# Sheet3_MCU.net
KiCad netlist of a schematic drawn in Altium Designer
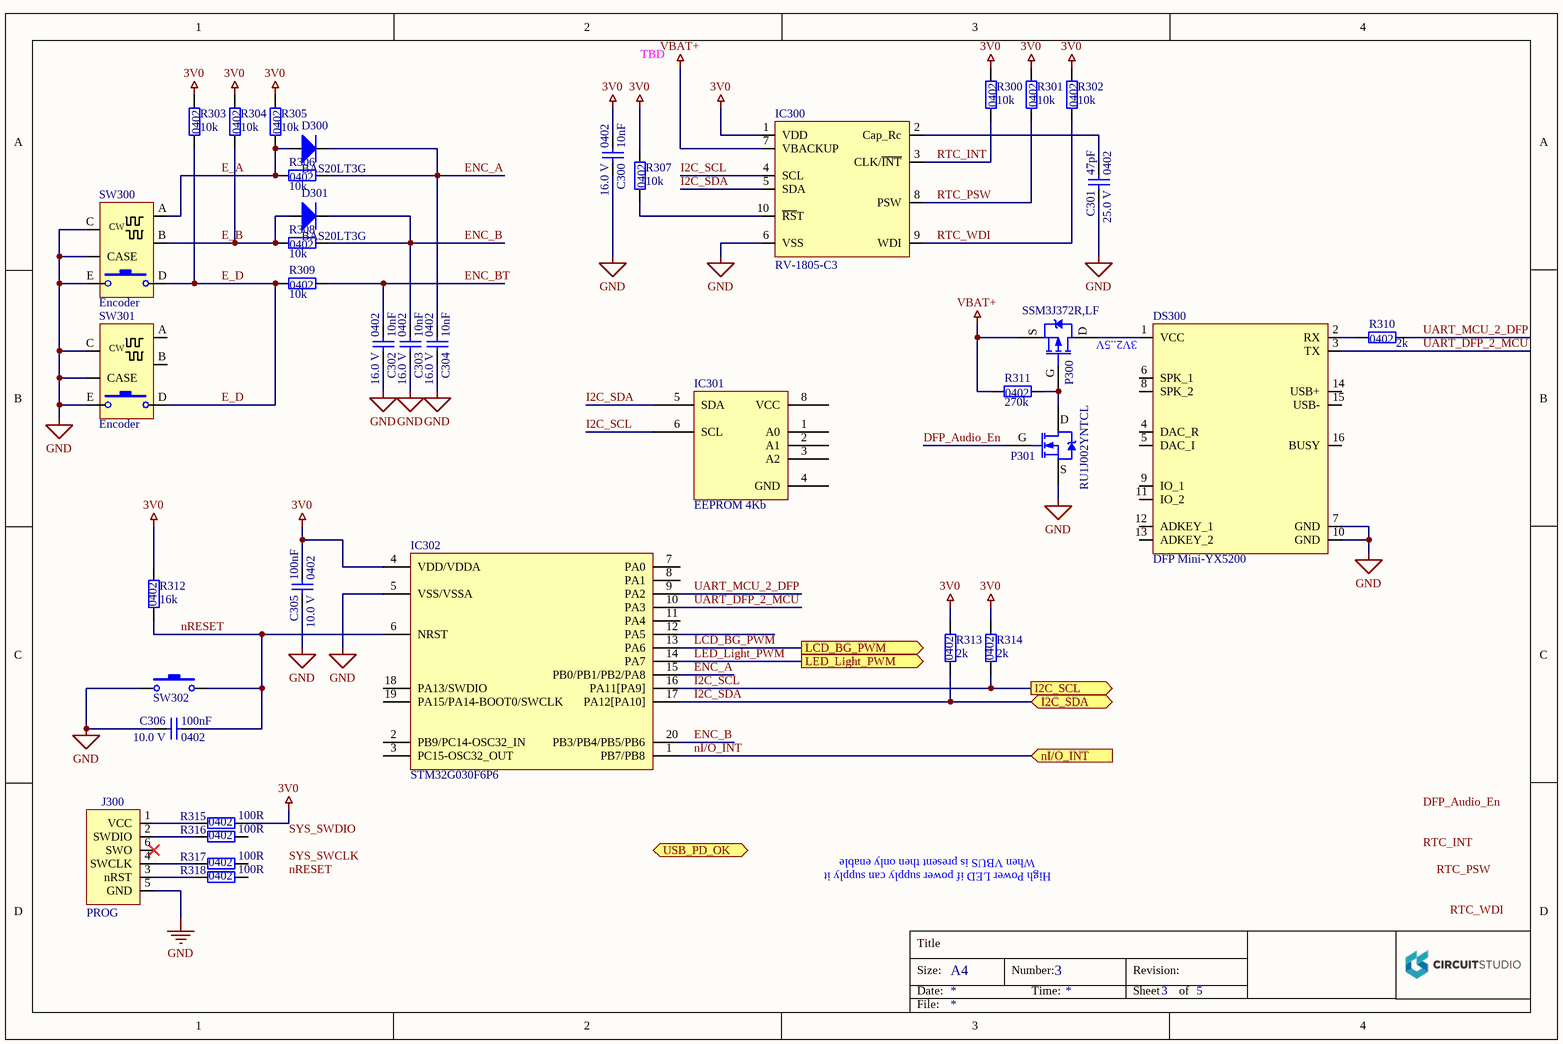
[diagram p0: Sheet3_MCU.SchDoc]

(export (version "E")
  (design (tool "Eeschema 10.0.6"))
  (components
    (comp (ref "C300")
      (value "C 10nF 0402 16V")
      (footprint "0402")
      (description "CAP CER 10000PF 16V Y5V 0402")
      (fields
        (field (name "MANUFACTURER") "Samsung Electro-Mechanics")
        (field (name "MANUFACTURER PART NUMBER") "CL05F103ZO5NNNC")
        (field (name "CAPACITANCE") "10nF")
        (field (name "VOLTAGE") "16.0 V")
      )
      (libsource (lib "CS_Part_Library") (part "CAP_10nF_16V_0402"))
    )
    (comp (ref "C301")
      (value "C 47pF 0402 25V")
      (footprint "0402")
      (description "CAP CER 47PF 25V C0G/NP0 0402")
      (fields
        (field (name "MANUFACTURER") "KEMET")
        (field (name "MANUFACTURER PART NUMBER") "C0402C470J3GAC7867")
        (field (name "CAPACITANCE") "47pF")
        (field (name "VOLTAGE") "25.0 V")
      )
      (libsource (lib "CS_Part_Library") (part "CAP_47pF_25V_0402"))
    )
    (comp (ref "C302")
      (value "C 10nF 0402 16V")
      (footprint "0402")
      (description "CAP CER 10000PF 16V Y5V 0402")
      (fields
        (field (name "MANUFACTURER") "Samsung Electro-Mechanics")
        (field (name "MANUFACTURER PART NUMBER") "CL05F103ZO5NNNC")
        (field (name "CAPACITANCE") "10nF")
        (field (name "VOLTAGE") "16.0 V")
      )
      (libsource (lib "CS_Part_Library") (part "CAP_10nF_16V_0402"))
    )
    (comp (ref "C303")
      (value "C 10nF 0402 16V")
      (footprint "0402")
      (description "CAP CER 10000PF 16V Y5V 0402")
      (fields
        (field (name "MANUFACTURER") "Samsung Electro-Mechanics")
        (field (name "MANUFACTURER PART NUMBER") "CL05F103ZO5NNNC")
        (field (name "CAPACITANCE") "10nF")
        (field (name "VOLTAGE") "16.0 V")
      )
      (libsource (lib "CS_Part_Library") (part "CAP_10nF_16V_0402"))
    )
    (comp (ref "C304")
      (value "C 10nF 0402 16V")
      (footprint "0402")
      (description "CAP CER 10000PF 16V Y5V 0402")
      (fields
        (field (name "MANUFACTURER") "Samsung Electro-Mechanics")
        (field (name "MANUFACTURER PART NUMBER") "CL05F103ZO5NNNC")
        (field (name "CAPACITANCE") "10nF")
        (field (name "VOLTAGE") "16.0 V")
      )
      (libsource (lib "CS_Part_Library") (part "CAP_10nF_16V_0402"))
    )
    (comp (ref "C305")
      (value "C 100nF 0402 10V")
      (footprint "0402")
      (description "CAP CER 0.1UF 10V X5R 0402")
      (fields
        (field (name "MANUFACTURER") "Samsung Electro-Mechanics")
        (field (name "MANUFACTURER PART NUMBER") "CL05A104MP5NNNC")
        (field (name "CAPACITANCE") "100nF")
        (field (name "VOLTAGE") "10.0 V")
      )
      (libsource (lib "CS_Part_Library") (part "CAP_100nF_10V_0402"))
    )
    (comp (ref "C306")
      (value "C 100nF 0402 10V")
      (footprint "0402")
      (description "CAP CER 0.1UF 10V X5R 0402")
      (fields
        (field (name "MANUFACTURER") "Samsung Electro-Mechanics")
        (field (name "MANUFACTURER PART NUMBER") "CL05A104MP5NNNC")
        (field (name "CAPACITANCE") "100nF")
        (field (name "VOLTAGE") "10.0 V")
      )
      (libsource (lib "CS_Part_Library") (part "CAP_100nF_10V_0402"))
    )
    (comp (ref "D300")
      (value "BAS20LT3G")
      (footprint "SOT-23-3")
      (description "DIODE GP 200V 200MA SOT23-3")
      (fields (field (name "MANUFACTURER") "onsemi") (field (name "MANUFACTURER PART NUMBER") "BAS20LT3G"))
      (libsource (lib "Symbols") (part "D_LL_200V_200mA"))
    )
    (comp (ref "D301")
      (value "BAS20LT3G")
      (footprint "SOT-23-3")
      (description "DIODE GP 200V 200MA SOT23-3")
      (fields (field (name "MANUFACTURER") "onsemi") (field (name "MANUFACTURER PART NUMBER") "BAS20LT3G"))
      (libsource (lib "Symbols") (part "D_LL_200V_200mA"))
    )
    (comp (ref "DS300")
      (value "DFP Mini-YX5200")
      (footprint "DFP_Player_Mini")
      (description "Mini-YX5200 Audio MP3 Modul")
      (fields (field (name "MANUFACTURER") "DFRobot") (field (name "MANUFACTURER PART NUMBER") "DFR0299"))
      (libsource (lib "CS_Part_Library") (part "DFP_Player_mini"))
    )
    (comp (ref "IC300")
      (value "RV-1805-C3")
      (footprint "SON-6")
      (description "IC RTC CLK/CALENDAR I2C 10SON")
      (fields
        (field (name "MANUFACTURER") "Micro Crystal AG")
        (field (name "MANUFACTURER PART NUMBER") "RV-1805-C3-32.768KHZ-2PPM-TA-QA")
      )
      (libsource (lib "CS_Part_Library") (part "IC_RTC_1805-C3"))
    )
    (comp (ref "IC301")
      (value "EEPROM 4Kb")
      (footprint "TSSOP-8_4.4mm")
      (description "IC EEPROM 4KBIT I2C 1MHZ 8TSSOP")
      (fields
        (field (name "MANUFACTURER") "Microchip Technology")
        (field (name "MANUFACTURER PART NUMBER") "AT34C04-X5M-T")
      )
      (libsource (lib "CS_Part_Library") (part "IC_EEPROM_4Kb"))
    )
    (comp (ref "IC302")
      (value "STM32G030F6P6")
      (footprint "TSSOP-20")
      (description "IC MCU 32BIT 32KB FLASH 20TSSOP")
      (fields (field (name "MANUFACTURER") "STMicroelectronics"))
      (libsource (lib "CS_Part_Library") (part "IC_MCU_STM32G030F6P6"))
    )
    (comp (ref "J300")
      (value "PROG")
      (footprint "J_TC2030-IDC-FP")
      (description "SWD Programmer")
      (fields (field (name "MANUFACTURER") "Tag_connect") (field (name "MANUFACTURER PART NUMBER") "TC2030"))
      (libsource (lib "CS_Part_Library") (part "J_TC2030-IDC-FP"))
    )
    (comp (ref "P300")
      (value "P PMOS 30V 6A")
      (footprint "SOT-23-3-F")
      (description "MOSFET P-CH 30V 6A SOT23F")
      (fields
        (field (name "MANUFACTURER") "Toshiba Semiconductor and Storage")
        (field (name "MANUFACTURER PART NUMBER") "SSM3J372R,LF")
      )
      (libsource (lib "CS_Part_Library") (part "P_PCH_30V_1W"))
    )
    (comp (ref "P301")
      (value "P_NCH_50V_150mW")
      (footprint "UMT3F")
      (description "MOSFET N-CH 50V 200MA UMT3F")
      (fields
        (field (name "MANUFACTURER") "Rohm Semiconductor")
        (field (name "MANUFACTURER PART NUMBER") "RU1J002YNTCL")
      )
      (libsource (lib "CS_Part_Library") (part "P_NCH_50V_150mW"))
    )
    (comp (ref "R300")
      (value "R 10k 0402")
      (footprint "0402")
      (description "RES 10K OHM 1% 1/16W 0402")
      (fields
        (field (name "MANUFACTURER") "YAGEO")
        (field (name "MANUFACTURER PART NUMBER") "RC0402FR-0710KL")
        (field (name "RESISTANCE") "10k")
      )
      (libsource (lib "CS_Part_Library") (part "R_10k_0402"))
    )
    (comp (ref "R301")
      (value "R 10k 0402")
      (footprint "0402")
      (description "RES 10K OHM 1% 1/16W 0402")
      (fields
        (field (name "MANUFACTURER") "YAGEO")
        (field (name "MANUFACTURER PART NUMBER") "RC0402FR-0710KL")
        (field (name "RESISTANCE") "10k")
      )
      (libsource (lib "CS_Part_Library") (part "R_10k_0402"))
    )
    (comp (ref "R302")
      (value "R 10k 0402")
      (footprint "0402")
      (description "RES 10K OHM 1% 1/16W 0402")
      (fields
        (field (name "MANUFACTURER") "YAGEO")
        (field (name "MANUFACTURER PART NUMBER") "RC0402FR-0710KL")
        (field (name "RESISTANCE") "10k")
      )
      (libsource (lib "CS_Part_Library") (part "R_10k_0402"))
    )
    (comp (ref "R303")
      (value "R 10k 0402")
      (footprint "0402")
      (description "RES 10K OHM 1% 1/16W 0402")
      (fields
        (field (name "MANUFACTURER") "YAGEO")
        (field (name "MANUFACTURER PART NUMBER") "RC0402FR-0710KL")
        (field (name "RESISTANCE") "10k")
      )
      (libsource (lib "CS_Part_Library") (part "R_10k_0402"))
    )
    (comp (ref "R304")
      (value "R 10k 0402")
      (footprint "0402")
      (description "RES 10K OHM 1% 1/16W 0402")
      (fields
        (field (name "MANUFACTURER") "YAGEO")
        (field (name "MANUFACTURER PART NUMBER") "RC0402FR-0710KL")
        (field (name "RESISTANCE") "10k")
      )
      (libsource (lib "CS_Part_Library") (part "R_10k_0402"))
    )
    (comp (ref "R305")
      (value "R 10k 0402")
      (footprint "0402")
      (description "RES 10K OHM 1% 1/16W 0402")
      (fields
        (field (name "MANUFACTURER") "YAGEO")
        (field (name "MANUFACTURER PART NUMBER") "RC0402FR-0710KL")
        (field (name "RESISTANCE") "10k")
      )
      (libsource (lib "CS_Part_Library") (part "R_10k_0402"))
    )
    (comp (ref "R306")
      (value "R 10k 0402")
      (footprint "0402")
      (description "RES 10K OHM 1% 1/16W 0402")
      (fields
        (field (name "MANUFACTURER") "YAGEO")
        (field (name "MANUFACTURER PART NUMBER") "RC0402FR-0710KL")
        (field (name "RESISTANCE") "10k")
      )
      (libsource (lib "") (part "R_10k_0402_1"))
    )
    (comp (ref "R307")
      (value "R 10k 0402")
      (footprint "0402")
      (description "RES 10K OHM 1% 1/16W 0402")
      (fields
        (field (name "MANUFACTURER") "YAGEO")
        (field (name "MANUFACTURER PART NUMBER") "RC0402FR-0710KL")
        (field (name "RESISTANCE") "10k")
      )
      (libsource (lib "CS_Part_Library") (part "R_10k_0402"))
    )
    (comp (ref "R308")
      (value "R 10k 0402")
      (footprint "0402")
      (description "RES 10K OHM 1% 1/16W 0402")
      (fields
        (field (name "MANUFACTURER") "YAGEO")
        (field (name "MANUFACTURER PART NUMBER") "RC0402FR-0710KL")
        (field (name "RESISTANCE") "10k")
      )
      (libsource (lib "") (part "R_10k_0402_1"))
    )
    (comp (ref "R309")
      (value "R 10k 0402")
      (footprint "0402")
      (description "RES 10K OHM 1% 1/16W 0402")
      (fields
        (field (name "MANUFACTURER") "YAGEO")
        (field (name "MANUFACTURER PART NUMBER") "RC0402FR-0710KL")
        (field (name "RESISTANCE") "10k")
      )
      (libsource (lib "") (part "R_10k_0402_1"))
    )
    (comp (ref "R310")
      (value "R 2k 0402")
      (footprint "0402")
      (description "RES 2K OHM 1% 1/16W 0402")
      (fields
        (field (name "MANUFACTURER") "Stackpole Electronics Inc")
        (field (name "MANUFACTURER PART NUMBER") "RMCF0402FT2K00")
        (field (name "RESISTANCE") "2k")
      )
      (libsource (lib "") (part "R_2k_0402_1"))
    )
    (comp (ref "R311")
      (value "R 270k 0402")
      (footprint "0402")
      (description "RES 270K OHM 1% 1/16W 0402")
      (fields
        (field (name "MANUFACTURER") "YAGEO")
        (field (name "MANUFACTURER PART NUMBER") "RC0402FR-07270KL")
        (field (name "RESISTANCE") "270k")
      )
      (libsource (lib "CS_Part_Library") (part "R_270k_0402"))
    )
    (comp (ref "R312")
      (value "R 16k 0402")
      (footprint "0402")
      (description "RES 16K OHM 1% 1/16W 0402")
      (fields
        (field (name "MANUFACTURER") "Stackpole Electronics Inc")
        (field (name "MANUFACTURER PART NUMBER") "RMCF0402FT16K0")
        (field (name "RESISTANCE") "16k")
      )
      (libsource (lib "CS_Part_Library") (part "R_16k_0402"))
    )
    (comp (ref "R313")
      (value "R 2k 0402")
      (footprint "0402")
      (description "RES 2K OHM 1% 1/16W 0402")
      (fields
        (field (name "MANUFACTURER") "Stackpole Electronics Inc")
        (field (name "MANUFACTURER PART NUMBER") "RMCF0402FT2K00")
        (field (name "RESISTANCE") "2k")
      )
      (libsource (lib "CS_Part_Library") (part "R_2k_0402"))
    )
    (comp (ref "R314")
      (value "R 2k 0402")
      (footprint "0402")
      (description "RES 2K OHM 1% 1/16W 0402")
      (fields
        (field (name "MANUFACTURER") "Stackpole Electronics Inc")
        (field (name "MANUFACTURER PART NUMBER") "RMCF0402FT2K00")
        (field (name "RESISTANCE") "2k")
      )
      (libsource (lib "CS_Part_Library") (part "R_2k_0402"))
    )
    (comp (ref "R315")
      (value "R 100R 0402")
      (footprint "0402")
      (description "RES 100 OHM 1% 1/16W 0402")
      (fields
        (field (name "MANUFACTURER") "Stackpole Electronics Inc")
        (field (name "MANUFACTURER PART NUMBER") "RMCF0402FT100R")
        (field (name "RESISTANCE") "100R")
      )
      (libsource (lib "Symbols") (part "R_100R_0402"))
    )
    (comp (ref "R316")
      (value "R 100R 0402")
      (footprint "0402")
      (description "RES 100 OHM 1% 1/16W 0402")
      (fields
        (field (name "MANUFACTURER") "Stackpole Electronics Inc")
        (field (name "MANUFACTURER PART NUMBER") "RMCF0402FT100R")
        (field (name "RESISTANCE") "100R")
      )
      (libsource (lib "Symbols") (part "R_100R_0402"))
    )
    (comp (ref "R317")
      (value "R 100R 0402")
      (footprint "0402")
      (description "RES 100 OHM 1% 1/16W 0402")
      (fields
        (field (name "MANUFACTURER") "Stackpole Electronics Inc")
        (field (name "MANUFACTURER PART NUMBER") "RMCF0402FT100R")
        (field (name "RESISTANCE") "100R")
      )
      (libsource (lib "Symbols") (part "R_100R_0402"))
    )
    (comp (ref "R318")
      (value "R 100R 0402")
      (footprint "0402")
      (description "RES 100 OHM 1% 1/16W 0402")
      (fields
        (field (name "MANUFACTURER") "Stackpole Electronics Inc")
        (field (name "MANUFACTURER PART NUMBER") "RMCF0402FT100R")
        (field (name "RESISTANCE") "100R")
      )
      (libsource (lib "Symbols") (part "R_100R_0402"))
    )
    (comp (ref "SW300")
      (value "Encoder")
      (footprint "PEC11R")
      (description "ROTARY ENCODER MECHANICAL 12PPR")
      (fields
        (field (name "MANUFACTURER") "Bourns Inc.")
        (field (name "MANUFACTURER PART NUMBER") "PEC11R-4220F-S0012")
      )
      (libsource (lib "CS_Part_Library") (part "ENC_12_THT"))
    )
    (comp (ref "SW301")
      (value "Encoder")
      (footprint "PEC11R")
      (description "ROTARY ENCODER MECHANICAL 12PPR")
      (fields
        (field (name "MANUFACTURER") "Bourns Inc.")
        (field (name "MANUFACTURER PART NUMBER") "PEC11R-4220F-S0012")
      )
      (libsource (lib "CS_Part_Library") (part "ENC_12_THT"))
    )
    (comp (ref "SW302")
      (value "SW")
      (footprint "SW_PTS810")
      (description "SWITCH TACTILE SPST-NO 0.05A 16V")
      (fields
        (field (name "MANUFACTURER") "C&K")
        (field (name "MANUFACTURER PART NUMBER") "PTS810 SJM 250 SMTR LFS")
      )
      (libsource (lib "CS_Part_Library") (part "SW_TactileSW_V"))
    )
  )
  (nets
    (net (code "1") (name "/DFP_Audio_En") (class "Default")
      (node (ref "P301") (pin "1") (pinfunction "G_1") (pintype "passive"))
    )
    (net (code "2") (name "/ENC_A") (class "Default")
      (node (ref "C304") (pin "2") (pinfunction "2_2") (pintype "passive"))
      (node (ref "D300") (pin "3") (pinfunction "K_3") (pintype "passive"))
      (node (ref "IC302") (pin "15") (pinfunction "PB0/PB1/PB2/PA8_15") (pintype "passive"))
      (node (ref "R306") (pin "2") (pinfunction "2_2") (pintype "passive"))
    )
    (net (code "3") (name "/ENC_B") (class "Default")
      (node (ref "C303") (pin "2") (pinfunction "2_2") (pintype "passive"))
      (node (ref "D301") (pin "3") (pinfunction "K_3") (pintype "passive"))
      (node (ref "IC302") (pin "20") (pinfunction "PB3/PB4/PB5/PB6_20") (pintype "passive"))
      (node (ref "R308") (pin "2") (pinfunction "2_2") (pintype "passive"))
    )
    (net (code "4") (name "/ENC_BT") (class "Default")
      (node (ref "C302") (pin "2") (pinfunction "2_2") (pintype "passive"))
      (node (ref "R309") (pin "2") (pinfunction "2_2") (pintype "passive"))
    )
    (net (code "5") (name "/E_A") (class "Default")
      (node (ref "D300") (pin "1") (pinfunction "A_1") (pintype "passive"))
      (node (ref "R305") (pin "1") (pinfunction "1_1") (pintype "passive"))
      (node (ref "R306") (pin "1") (pinfunction "1_1") (pintype "passive"))
      (node (ref "SW300") (pin "A") (pinfunction "A_A") (pintype "passive"))
    )
    (net (code "6") (name "/E_B") (class "Default")
      (node (ref "D301") (pin "1") (pinfunction "A_1") (pintype "passive"))
      (node (ref "R304") (pin "1") (pinfunction "1_1") (pintype "passive"))
      (node (ref "R308") (pin "1") (pinfunction "1_1") (pintype "passive"))
      (node (ref "SW300") (pin "B") (pinfunction "B_B") (pintype "passive"))
    )
    (net (code "7") (name "/E_D") (class "Default")
      (node (ref "R303") (pin "1") (pinfunction "1_1") (pintype "passive"))
      (node (ref "R309") (pin "1") (pinfunction "1_1") (pintype "passive"))
      (node (ref "SW300") (pin "D") (pinfunction "D_D") (pintype "passive"))
      (node (ref "SW301") (pin "D") (pinfunction "D_D") (pintype "passive"))
    )
    (net (code "8") (name "/I2C_SCL") (class "Default")
      (node (ref "IC300") (pin "4") (pinfunction "SCL_4") (pintype "passive"))
      (node (ref "IC301") (pin "6") (pinfunction "SCL_6") (pintype "passive"))
      (node (ref "IC302") (pin "16") (pinfunction "PA11[PA9]_16") (pintype "passive"))
      (node (ref "R314") (pin "1") (pinfunction "1_1") (pintype "passive"))
    )
    (net (code "9") (name "/I2C_SDA") (class "Default")
      (node (ref "IC300") (pin "5") (pinfunction "SDA_5") (pintype "passive"))
      (node (ref "IC301") (pin "5") (pinfunction "SDA_5") (pintype "passive"))
      (node (ref "IC302") (pin "17") (pinfunction "PA12[PA10]_17") (pintype "passive"))
      (node (ref "R313") (pin "1") (pinfunction "1_1") (pintype "passive"))
    )
    (net (code "10") (name "/LCD_BG_PWM") (class "Default")
      (node (ref "IC302") (pin "13") (pinfunction "PA6_13") (pintype "passive"))
    )
    (net (code "11") (name "/LED_Light_PWM") (class "Default")
      (node (ref "IC302") (pin "14") (pinfunction "PA7_14") (pintype "passive"))
    )
    (net (code "12") (name "/RTC_INT") (class "Default")
      (node (ref "IC300") (pin "3") (pinfunction "CLK/~{INT}_3") (pintype "passive"))
      (node (ref "R300") (pin "1") (pinfunction "1_1") (pintype "passive"))
    )
    (net (code "13") (name "/RTC_PSW") (class "Default")
      (node (ref "IC300") (pin "8") (pinfunction "PSW_8") (pintype "passive"))
      (node (ref "R301") (pin "1") (pinfunction "1_1") (pintype "passive"))
    )
    (net (code "14") (name "/RTC_WDI") (class "Default")
      (node (ref "IC300") (pin "9") (pinfunction "WDI_9") (pintype "passive"))
      (node (ref "R302") (pin "1") (pinfunction "1_1") (pintype "passive"))
    )
    (net (code "17") (name "/UART_DFP_2_MCU") (class "Default")
      (node (ref "DS300") (pin "3") (pinfunction "TX_3") (pintype "passive"))
      (node (ref "IC302") (pin "10") (pinfunction "PA3_10") (pintype "passive"))
    )
    (net (code "18") (name "/UART_MCU_2_DFP") (class "Default")
      (node (ref "IC302") (pin "9") (pinfunction "PA2_9") (pintype "passive"))
      (node (ref "R310") (pin "1") (pinfunction "1_1") (pintype "passive"))
    )
    (net (code "20") (name "/nI{slash}O_INT") (class "Default")
      (node (ref "IC302") (pin "1") (pinfunction "PB7/PB8_1") (pintype "passive"))
    )
    (net (code "21") (name "/nRESET") (class "Default")
      (node (ref "C306") (pin "2") (pinfunction "2_2") (pintype "passive"))
      (node (ref "IC302") (pin "6") (pinfunction "NRST_6") (pintype "passive"))
      (node (ref "R312") (pin "1") (pinfunction "1_1") (pintype "passive"))
      (node (ref "SW302") (pin "3") (pinfunction "2,_3_3") (pintype "passive"))
    )
    (net (code "22") (name "3V0") (class "Default")
      (node (ref "C300") (pin "2") (pinfunction "2_2") (pintype "passive"))
      (node (ref "C305") (pin "2") (pinfunction "2_2") (pintype "passive"))
      (node (ref "IC300") (pin "1") (pinfunction "VDD_1") (pintype "passive"))
      (node (ref "IC302") (pin "4") (pinfunction "VDD/VDDA_4") (pintype "passive"))
      (node (ref "R300") (pin "2") (pinfunction "2_2") (pintype "passive"))
      (node (ref "R301") (pin "2") (pinfunction "2_2") (pintype "passive"))
      (node (ref "R302") (pin "2") (pinfunction "2_2") (pintype "passive"))
      (node (ref "R303") (pin "2") (pinfunction "2_2") (pintype "passive"))
      (node (ref "R304") (pin "2") (pinfunction "2_2") (pintype "passive"))
      (node (ref "R305") (pin "2") (pinfunction "2_2") (pintype "passive"))
      (node (ref "R307") (pin "2") (pinfunction "2_2") (pintype "passive"))
      (node (ref "R312") (pin "2") (pinfunction "2_2") (pintype "passive"))
      (node (ref "R313") (pin "2") (pinfunction "2_2") (pintype "passive"))
      (node (ref "R314") (pin "2") (pinfunction "2_2") (pintype "passive"))
      (node (ref "R315") (pin "2") (pinfunction "2_2") (pintype "passive"))
    )
    (net (code "23") (name "GND") (class "Default")
      (node (ref "C300") (pin "1") (pinfunction "1_1") (pintype "passive"))
      (node (ref "C301") (pin "1") (pinfunction "1_1") (pintype "passive"))
      (node (ref "C302") (pin "1") (pinfunction "1_1") (pintype "passive"))
      (node (ref "C303") (pin "1") (pinfunction "1_1") (pintype "passive"))
      (node (ref "C304") (pin "1") (pinfunction "1_1") (pintype "passive"))
      (node (ref "C305") (pin "1") (pinfunction "1_1") (pintype "passive"))
      (node (ref "C306") (pin "1") (pinfunction "1_1") (pintype "passive"))
      (node (ref "DS300") (pin "10") (pinfunction "GND_10") (pintype "passive"))
      (node (ref "DS300") (pin "7") (pinfunction "GND_7") (pintype "passive"))
      (node (ref "IC300") (pin "6") (pinfunction "VSS_6") (pintype "passive"))
      (node (ref "IC302") (pin "5") (pinfunction "VSS/VSSA_5") (pintype "passive"))
      (node (ref "J300") (pin "5") (pinfunction "GND_5") (pintype "passive"))
      (node (ref "P301") (pin "2") (pinfunction "S_2") (pintype "passive"))
      (node (ref "SW300") (pin "C") (pinfunction "C_C") (pintype "passive"))
      (node (ref "SW300") (pin "CASE") (pinfunction "CASE_CASE") (pintype "passive"))
      (node (ref "SW300") (pin "E") (pinfunction "E_E") (pintype "passive"))
      (node (ref "SW301") (pin "C") (pinfunction "C_C") (pintype "passive"))
      (node (ref "SW301") (pin "CASE") (pinfunction "CASE_CASE") (pintype "passive"))
      (node (ref "SW301") (pin "E") (pinfunction "E_E") (pintype "passive"))
      (node (ref "SW302") (pin "1") (pinfunction "1,_2_1") (pintype "passive"))
    )
    (net (code "24") (name "Net-(DS300-RX)") (class "Default")
      (node (ref "DS300") (pin "2") (pinfunction "RX_2") (pintype "passive"))
      (node (ref "R310") (pin "2") (pinfunction "2_2") (pintype "passive"))
    )
    (net (code "25") (name "Net-(DS300-VCC)") (class "Default")
      (node (ref "DS300") (pin "1") (pinfunction "VCC_1") (pintype "passive"))
      (node (ref "P300") (pin "3") (pinfunction "D_3") (pintype "passive"))
    )
    (net (code "26") (name "Net-(IC300-Cap_Rc)") (class "Default")
      (node (ref "C301") (pin "2") (pinfunction "2_2") (pintype "passive"))
      (node (ref "IC300") (pin "2") (pinfunction "Cap_Rc_2") (pintype "passive"))
    )
    (net (code "27") (name "Net-(IC300-~{RS}T)") (class "Default")
      (node (ref "IC300") (pin "10") (pinfunction "~{RS}T_10") (pintype "passive"))
      (node (ref "R307") (pin "1") (pinfunction "1_1") (pintype "passive"))
    )
    (net (code "28") (name "Net-(J300-SWCLK)") (class "Default")
      (node (ref "J300") (pin "4") (pinfunction "SWCLK_4") (pintype "passive"))
      (node (ref "R317") (pin "1") (pinfunction "1_1") (pintype "passive"))
    )
    (net (code "29") (name "Net-(J300-SWDIO)") (class "Default")
      (node (ref "J300") (pin "2") (pinfunction "SWDIO_2") (pintype "passive"))
      (node (ref "R316") (pin "1") (pinfunction "1_1") (pintype "passive"))
    )
    (net (code "30") (name "Net-(J300-VCC)") (class "Default")
      (node (ref "J300") (pin "1") (pinfunction "VCC_1") (pintype "passive"))
      (node (ref "R315") (pin "1") (pinfunction "1_1") (pintype "passive"))
    )
    (net (code "31") (name "Net-(J300-nRST)") (class "Default")
      (node (ref "J300") (pin "3") (pinfunction "nRST_3") (pintype "passive"))
      (node (ref "R318") (pin "1") (pinfunction "1_1") (pintype "passive"))
    )
    (net (code "32") (name "Net-(P300-G)") (class "Default")
      (node (ref "P300") (pin "1") (pinfunction "G_1") (pintype "passive"))
      (node (ref "P301") (pin "3") (pinfunction "D_3") (pintype "passive"))
      (node (ref "R311") (pin "1") (pinfunction "1_1") (pintype "passive"))
    )
    (net (code "33") (name "VBAT+") (class "Default")
      (node (ref "IC300") (pin "7") (pinfunction "VBACKUP_7") (pintype "passive"))
      (node (ref "P300") (pin "2") (pinfunction "S_2") (pintype "passive"))
      (node (ref "R311") (pin "2") (pinfunction "2_2") (pintype "passive"))
    )
    (net (code "34") (name "unconnected-(DS300-ADKEY_1-Pad12)") (class "Default")
      (node (ref "DS300") (pin "12") (pinfunction "ADKEY_1_12") (pintype "passive"))
    )
    (net (code "35") (name "unconnected-(DS300-ADKEY_2-Pad13)") (class "Default")
      (node (ref "DS300") (pin "13") (pinfunction "ADKEY_2_13") (pintype "passive"))
    )
    (net (code "36") (name "unconnected-(DS300-BUSY-Pad16)") (class "Default")
      (node (ref "DS300") (pin "16") (pinfunction "BUSY_16") (pintype "passive"))
    )
    (net (code "37") (name "unconnected-(DS300-DAC_I-Pad5)") (class "Default")
      (node (ref "DS300") (pin "5") (pinfunction "DAC_I_5") (pintype "passive"))
    )
    (net (code "38") (name "unconnected-(DS300-DAC_R-Pad4)") (class "Default")
      (node (ref "DS300") (pin "4") (pinfunction "DAC_R_4") (pintype "passive"))
    )
    (net (code "39") (name "unconnected-(DS300-IO_1-Pad9)") (class "Default")
      (node (ref "DS300") (pin "9") (pinfunction "IO_1_9") (pintype "passive"))
    )
    (net (code "40") (name "unconnected-(DS300-IO_2-Pad11)") (class "Default")
      (node (ref "DS300") (pin "11") (pinfunction "IO_2_11") (pintype "passive"))
    )
    (net (code "41") (name "unconnected-(DS300-SPK_1-Pad6)") (class "Default")
      (node (ref "DS300") (pin "6") (pinfunction "SPK_1_6") (pintype "passive"))
    )
    (net (code "42") (name "unconnected-(DS300-SPK_2-Pad8)") (class "Default")
      (node (ref "DS300") (pin "8") (pinfunction "SPK_2_8") (pintype "passive"))
    )
    (net (code "43") (name "unconnected-(DS300-USB+-Pad14)") (class "Default")
      (node (ref "DS300") (pin "14") (pinfunction "USB+_14") (pintype "passive"))
    )
    (net (code "44") (name "unconnected-(DS300-USB--Pad15)") (class "Default")
      (node (ref "DS300") (pin "15") (pinfunction "USB-_15") (pintype "passive"))
    )
    (net (code "45") (name "unconnected-(IC301-A0-Pad1)") (class "Default")
      (node (ref "IC301") (pin "1") (pinfunction "A0_1") (pintype "passive"))
    )
    (net (code "46") (name "unconnected-(IC301-A1-Pad2)") (class "Default")
      (node (ref "IC301") (pin "2") (pinfunction "A1_2") (pintype "passive"))
    )
    (net (code "47") (name "unconnected-(IC301-A2-Pad3)") (class "Default")
      (node (ref "IC301") (pin "3") (pinfunction "A2_3") (pintype "passive"))
    )
    (net (code "48") (name "unconnected-(IC301-GND-Pad4)") (class "Default")
      (node (ref "IC301") (pin "4") (pinfunction "GND_4") (pintype "passive"))
    )
    (net (code "49") (name "unconnected-(IC301-VCC-Pad8)") (class "Default")
      (node (ref "IC301") (pin "8") (pinfunction "VCC_8") (pintype "passive"))
    )
    (net (code "50") (name "unconnected-(IC302-PA0-Pad7)") (class "Default")
      (node (ref "IC302") (pin "7") (pinfunction "PA0_7") (pintype "passive"))
    )
    (net (code "51") (name "unconnected-(IC302-PA1-Pad8)") (class "Default")
      (node (ref "IC302") (pin "8") (pinfunction "PA1_8") (pintype "passive"))
    )
    (net (code "52") (name "unconnected-(IC302-PA4-Pad11)") (class "Default")
      (node (ref "IC302") (pin "11") (pinfunction "PA4_11") (pintype "passive"))
    )
    (net (code "53") (name "unconnected-(IC302-PA5-Pad12)") (class "Default")
      (node (ref "IC302") (pin "12") (pinfunction "PA5_12") (pintype "passive"))
    )
    (net (code "54") (name "unconnected-(IC302-PA13{slash}SWDIO-Pad18)") (class "Default")
      (node (ref "IC302") (pin "18") (pinfunction "PA13/SWDIO_18") (pintype "passive"))
    )
    (net (code "55") (name "unconnected-(IC302-PA15{slash}PA14-BOOT0{slash}SWCLK-Pad19)") (class "Default")
      (node (ref "IC302") (pin "19") (pinfunction "PA15/PA14-BOOT0/SWCLK_19") (pintype "passive"))
    )
    (net (code "56") (name "unconnected-(IC302-PB9{slash}PC14-OSC32_IN-Pad2)") (class "Default")
      (node (ref "IC302") (pin "2") (pinfunction "PB9/PC14-OSC32_IN_2") (pintype "passive"))
    )
    (net (code "57") (name "unconnected-(IC302-PC15-OSC32_OUT-Pad3)") (class "Default")
      (node (ref "IC302") (pin "3") (pinfunction "PC15-OSC32_OUT_3") (pintype "passive"))
    )
    (net (code "58") (name "unconnected-(J300-SWO-Pad6)") (class "Default")
      (node (ref "J300") (pin "6") (pinfunction "SWO_6") (pintype "passive+no_connect"))
    )
    (net (code "59") (name "unconnected-(R316-Pad2)") (class "Default")
      (node (ref "R316") (pin "2") (pinfunction "2_2") (pintype "passive"))
    )
    (net (code "60") (name "unconnected-(R317-Pad2)") (class "Default")
      (node (ref "R317") (pin "2") (pinfunction "2_2") (pintype "passive"))
    )
    (net (code "61") (name "unconnected-(R318-Pad2)") (class "Default")
      (node (ref "R318") (pin "2") (pinfunction "2_2") (pintype "passive"))
    )
    (net (code "62") (name "unconnected-(SW301-PadA)") (class "Default")
      (node (ref "SW301") (pin "A") (pinfunction "A_A") (pintype "passive"))
    )
    (net (code "63") (name "unconnected-(SW301-PadB)") (class "Default")
      (node (ref "SW301") (pin "B") (pinfunction "B_B") (pintype "passive"))
    )
  )
)
